# dongle.net
KiCad netlist of a schematic drawn in EAGLE
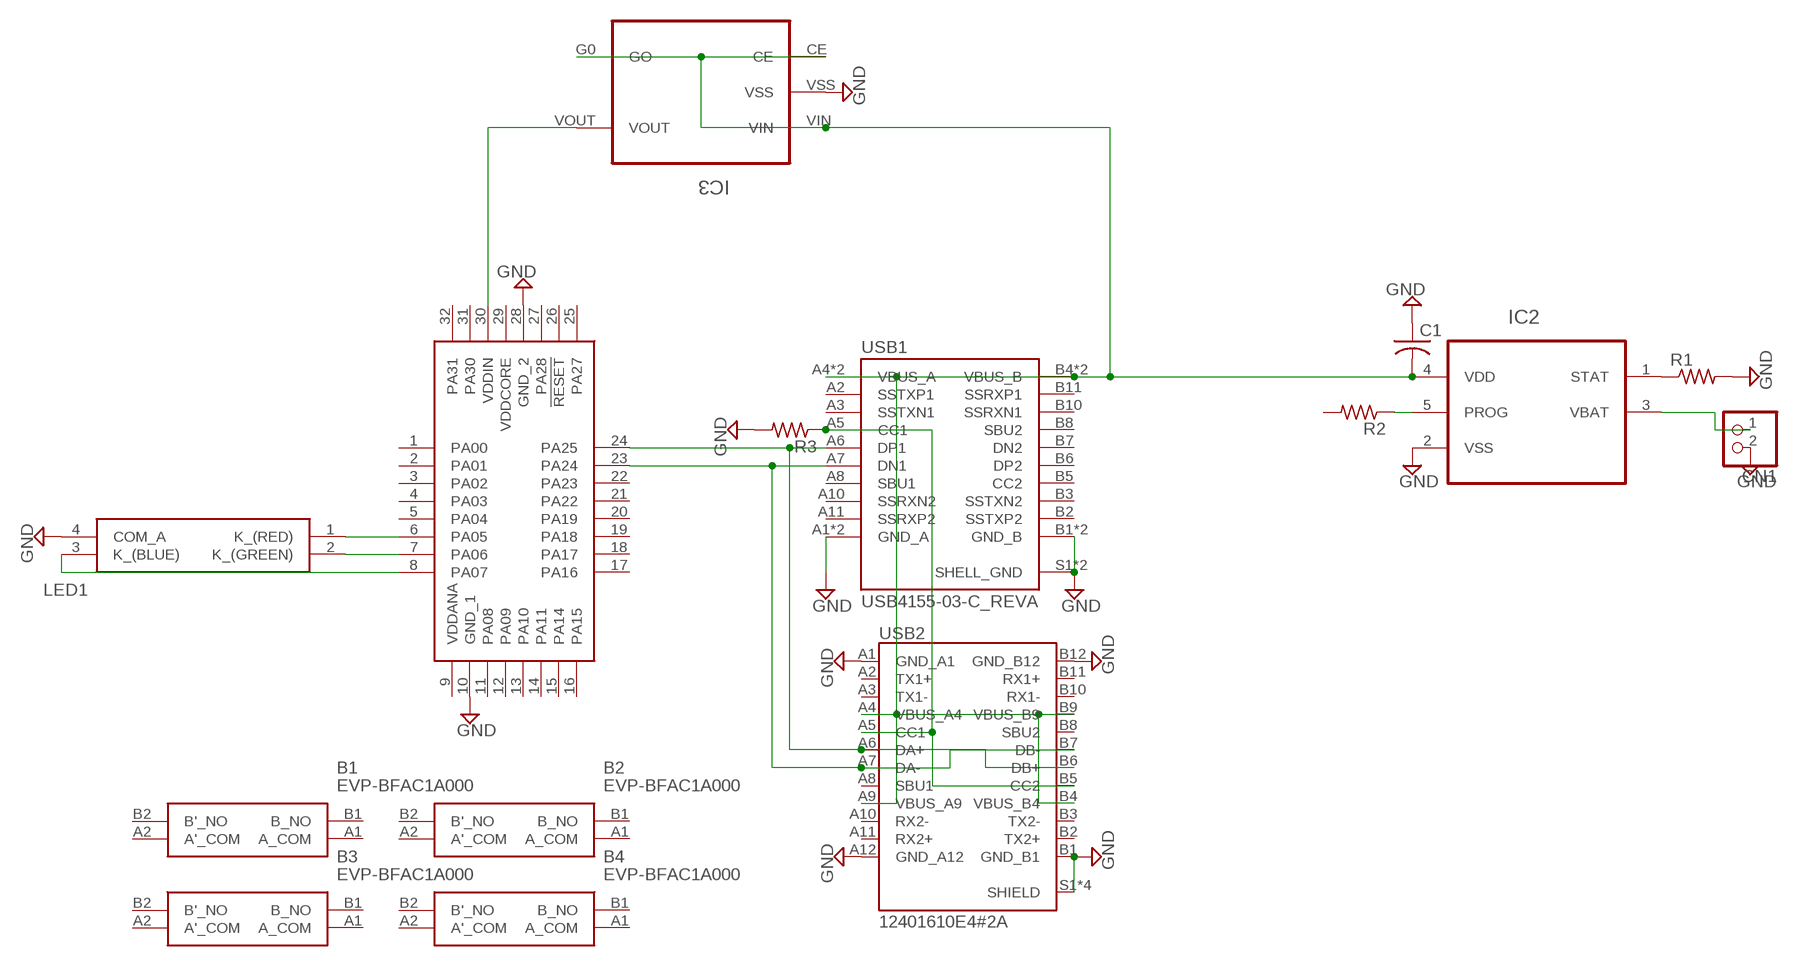
[diagram p0: schematic, sheet 1]

(export (version "E")
  (design (tool "Eeschema 10.0.6"))
  (components
    (comp (ref "B1")
      (value "EVP-BFAC1A000")
      (footprint "eagle-import:EVPBFAC1A000")
      (fields (field (name "MOUSER_PART_NUMBER") "667-EVP-BFAC1A000"))
      (libsource (lib "eagle-import") (part "EVP-BFAC1A000"))
    )
    (comp (ref "B2")
      (value "EVP-BFAC1A000")
      (footprint "eagle-import:EVPBFAC1A000")
      (fields (field (name "MOUSER_PART_NUMBER") "667-EVP-BFAC1A000"))
      (libsource (lib "eagle-import") (part "EVP-BFAC1A000"))
    )
    (comp (ref "B3")
      (value "EVP-BFAC1A000")
      (footprint "eagle-import:EVPBFAC1A000")
      (fields (field (name "MOUSER_PART_NUMBER") "667-EVP-BFAC1A000"))
      (libsource (lib "eagle-import") (part "EVP-BFAC1A000"))
    )
    (comp (ref "B4")
      (value "EVP-BFAC1A000")
      (footprint "eagle-import:EVPBFAC1A000")
      (fields (field (name "MOUSER_PART_NUMBER") "667-EVP-BFAC1A000"))
      (libsource (lib "eagle-import") (part "EVP-BFAC1A000"))
    )
    (comp (ref "C1")
      (value "C-USC0805")
      (footprint "eagle-import:C0805")
      (libsource (lib "eagle-import") (part "C-USC0805"))
    )
    (comp (ref "CN1")
      (value "JST_2PIN-SMT-RA")
      (footprint "eagle-import:JST-PH-2-SMT-RA")
      (libsource (lib "eagle-import") (part "JST_2PIN-SMT-RA"))
    )
    (comp (ref "IC1")
      (value "ATSAMD21E18A-AFT")
      (footprint "eagle-import:QFP80P900X900X120-32N")
      (fields (field (name "MOUSER_PART_NUMBER") "556-ATSAMD21E18A-AFT"))
      (libsource (lib "eagle-import") (part "ATSAMD21E18A-AFT"))
    )
    (comp (ref "IC2")
      (value "MCP73831T-2ACI/OT")
      (footprint "eagle-import:SOT95P280X145-5N")
      (fields (field (name "MF") "Microchip"))
      (libsource (lib "eagle-import") (part "MCP73831T-2ACI/OT"))
    )
    (comp (ref "IC3")
      (value "IC_XC8107AC20MR-G")
      (footprint "eagle-import:IC_XC8107AC20MR-G")
      (libsource (lib "eagle-import") (part "IC_XC8107AC20MR-G"))
    )
    (comp (ref "LED1")
      (value "ASMB-MTB1-0B3A2")
      (footprint "eagle-import:ASMBMTB10B3A2")
      (fields (field (name "MOUSER_PART_NUMBER") "630-ASMB-MTB1-0B3A2"))
      (libsource (lib "eagle-import") (part "ASMB-MTB1-0B3A2"))
    )
    (comp (ref "R1")
      (value "R-US_R0805")
      (footprint "eagle-import:R0805")
      (libsource (lib "eagle-import") (part "R-US_R0805"))
    )
    (comp (ref "R2")
      (value "R-US_R0805")
      (footprint "eagle-import:R0805")
      (libsource (lib "eagle-import") (part "R-US_R0805"))
    )
    (comp (ref "R3")
      (value "R-US_R0805")
      (footprint "eagle-import:R0805")
      (libsource (lib "eagle-import") (part "R-US_R0805"))
    )
    (comp (ref "USB1")
      (value "USB4155-03-C_REVA")
      (footprint "eagle-import:GCT_USB4155-03-C_REVA")
      (fields (field (name "MF") "Global Connector Technology") (field (name "MP") "USB4155-03-C"))
      (libsource (lib "eagle-import") (part "USB4155-03-C_REVA"))
    )
    (comp (ref "USB2")
      (value "12401610E4#2A")
      (footprint "eagle-import:AMPHENOL_12401610E4#2A")
      (fields (field (name "MF") "Amphenol ICC (Commercial Products)"))
      (libsource (lib "eagle-import") (part "12401610E4#2A"))
    )
  )
  (nets
    (net (code "1") (name "GND") (class "Default")
      (node (ref "C1") (pin "1") (pinfunction "1_1") (pintype "passive"))
      (node (ref "CN1") (pin "2") (pinfunction "1_2") (pintype "passive"))
      (node (ref "IC1") (pin "10") (pinfunction "GND_1_10") (pintype "bidirectional"))
      (node (ref "IC1") (pin "28") (pinfunction "GND_2_28") (pintype "bidirectional"))
      (node (ref "IC2") (pin "2") (pinfunction "VSS_2") (pintype "power_in"))
      (node (ref "IC3") (pin "VSS") (pinfunction "VSS_VSS") (pintype "input"))
      (node (ref "LED1") (pin "4") (pinfunction "COM_A_4") (pintype "bidirectional"))
      (node (ref "R1") (pin "2") (pinfunction "2_2") (pintype "passive"))
      (node (ref "R3") (pin "2") (pinfunction "2_2") (pintype "passive"))
      (node (ref "USB1") (pin "A1") (pinfunction "GND_A_A1") (pintype "power_in"))
      (node (ref "USB1") (pin "A12") (pinfunction "GND_A_A12") (pintype "power_in"))
      (node (ref "USB1") (pin "B1") (pinfunction "GND_B_B1") (pintype "power_in"))
      (node (ref "USB1") (pin "B12") (pinfunction "GND_B_B12") (pintype "power_in"))
      (node (ref "USB1") (pin "S1") (pinfunction "SHELL_GND_S1") (pintype "power_in"))
      (node (ref "USB1") (pin "S2") (pinfunction "SHELL_GND_S2") (pintype "power_in"))
      (node (ref "USB2") (pin "A1") (pinfunction "GND_A1_A1") (pintype "passive"))
      (node (ref "USB2") (pin "A12") (pinfunction "GND_A12_A12") (pintype "passive"))
      (node (ref "USB2") (pin "B1") (pinfunction "GND_B1_B1") (pintype "passive"))
      (node (ref "USB2") (pin "B12") (pinfunction "GND_B12_B12") (pintype "passive"))
      (node (ref "USB2") (pin "S1") (pinfunction "SHIELD_S1") (pintype "passive"))
      (node (ref "USB2") (pin "S2") (pinfunction "SHIELD_S2") (pintype "passive"))
      (node (ref "USB2") (pin "S3") (pinfunction "SHIELD_S3") (pintype "passive"))
      (node (ref "USB2") (pin "S4") (pinfunction "SHIELD_S4") (pintype "passive"))
    )
    (net (code "2") (name "Net-(CN1-2)") (class "Default")
      (node (ref "CN1") (pin "1") (pinfunction "2_1") (pintype "passive"))
      (node (ref "IC2") (pin "3") (pinfunction "VBAT_3") (pintype "output"))
    )
    (net (code "3") (name "Net-(IC1-PA05)") (class "Default")
      (node (ref "IC1") (pin "6") (pinfunction "PA05_6") (pintype "bidirectional"))
      (node (ref "LED1") (pin "1") (pinfunction "K_(RED)_1") (pintype "bidirectional"))
    )
    (net (code "4") (name "Net-(IC1-PA06)") (class "Default")
      (node (ref "IC1") (pin "7") (pinfunction "PA06_7") (pintype "bidirectional"))
      (node (ref "LED1") (pin "2") (pinfunction "K_(GREEN)_2") (pintype "bidirectional"))
    )
    (net (code "5") (name "Net-(IC1-PA07)") (class "Default")
      (node (ref "IC1") (pin "8") (pinfunction "PA07_8") (pintype "bidirectional"))
      (node (ref "LED1") (pin "3") (pinfunction "K_(BLUE)_3") (pintype "bidirectional"))
    )
    (net (code "6") (name "Net-(IC1-PA24)") (class "Default")
      (node (ref "IC1") (pin "23") (pinfunction "PA24_23") (pintype "bidirectional"))
      (node (ref "USB1") (pin "A7") (pinfunction "DN1_A7") (pintype "bidirectional"))
      (node (ref "USB2") (pin "A7") (pinfunction "DA-_A7") (pintype "passive"))
      (node (ref "USB2") (pin "B7") (pinfunction "DB-_B7") (pintype "passive"))
    )
    (net (code "7") (name "Net-(IC1-PA25)") (class "Default")
      (node (ref "IC1") (pin "24") (pinfunction "PA25_24") (pintype "bidirectional"))
      (node (ref "USB1") (pin "A6") (pinfunction "DP1_A6") (pintype "bidirectional"))
      (node (ref "USB2") (pin "A6") (pinfunction "DA+_A6") (pintype "passive"))
      (node (ref "USB2") (pin "B6") (pinfunction "DB+_B6") (pintype "passive"))
    )
    (net (code "8") (name "Net-(IC1-VDDIN)") (class "Default")
      (node (ref "IC1") (pin "30") (pinfunction "VDDIN_30") (pintype "bidirectional"))
      (node (ref "IC3") (pin "VOUT") (pinfunction "VOUT_VOUT") (pintype "output"))
    )
    (net (code "9") (name "Net-(IC2-PROG)") (class "Default")
      (node (ref "IC2") (pin "5") (pinfunction "PROG_5") (pintype "input"))
      (node (ref "R2") (pin "1") (pinfunction "1_1") (pintype "passive"))
    )
    (net (code "10") (name "Net-(IC2-STAT)") (class "Default")
      (node (ref "IC2") (pin "1") (pinfunction "STAT_1") (pintype "output"))
      (node (ref "R1") (pin "1") (pinfunction "1_1") (pintype "passive"))
    )
    (net (code "11") (name "Net-(IC2-VDD)") (class "Default")
      (node (ref "C1") (pin "2") (pinfunction "2_2") (pintype "passive"))
      (node (ref "IC2") (pin "4") (pinfunction "VDD_4") (pintype "power_in"))
      (node (ref "IC3") (pin "CE") (pinfunction "CE_CE") (pintype "power_in"))
      (node (ref "IC3") (pin "G0") (pinfunction "GO_G0") (pintype "output"))
      (node (ref "IC3") (pin "VIN") (pinfunction "VIN_VIN") (pintype "power_in"))
      (node (ref "USB1") (pin "A4") (pinfunction "VBUS_A_A4") (pintype "power_in"))
      (node (ref "USB1") (pin "A9") (pinfunction "VBUS_A_A9") (pintype "power_in"))
      (node (ref "USB1") (pin "B4") (pinfunction "VBUS_B_B4") (pintype "power_in"))
      (node (ref "USB1") (pin "B9") (pinfunction "VBUS_B_B9") (pintype "power_in"))
      (node (ref "USB2") (pin "A4") (pinfunction "VBUS_A4_A4") (pintype "passive"))
      (node (ref "USB2") (pin "A9") (pinfunction "VBUS_A9_A9") (pintype "passive"))
      (node (ref "USB2") (pin "B4") (pinfunction "VBUS_B4_B4") (pintype "passive"))
      (node (ref "USB2") (pin "B9") (pinfunction "VBUS_B9_B9") (pintype "passive"))
    )
    (net (code "12") (name "Net-(USB1-CC1)") (class "Default")
      (node (ref "R3") (pin "1") (pinfunction "1_1") (pintype "passive"))
      (node (ref "USB1") (pin "A5") (pinfunction "CC1_A5") (pintype "bidirectional"))
      (node (ref "USB2") (pin "A5") (pinfunction "CC1_A5") (pintype "passive"))
      (node (ref "USB2") (pin "B5") (pinfunction "CC2_B5") (pintype "passive"))
    )
    (net (code "13") (name "unconnected-(B1-A'_COM-PadA2)") (class "Default")
      (node (ref "B1") (pin "A2") (pinfunction "A'_COM_A2") (pintype "bidirectional"))
    )
    (net (code "14") (name "unconnected-(B1-A_COM-PadA1)") (class "Default")
      (node (ref "B1") (pin "A1") (pinfunction "A_COM_A1") (pintype "bidirectional"))
    )
    (net (code "15") (name "unconnected-(B1-B'_NO-PadB2)") (class "Default")
      (node (ref "B1") (pin "B2") (pinfunction "B'_NO_B2") (pintype "bidirectional"))
    )
    (net (code "16") (name "unconnected-(B1-B_NO-PadB1)") (class "Default")
      (node (ref "B1") (pin "B1") (pinfunction "B_NO_B1") (pintype "bidirectional"))
    )
    (net (code "17") (name "unconnected-(B2-A'_COM-PadA2)") (class "Default")
      (node (ref "B2") (pin "A2") (pinfunction "A'_COM_A2") (pintype "bidirectional"))
    )
    (net (code "18") (name "unconnected-(B2-A_COM-PadA1)") (class "Default")
      (node (ref "B2") (pin "A1") (pinfunction "A_COM_A1") (pintype "bidirectional"))
    )
    (net (code "19") (name "unconnected-(B2-B'_NO-PadB2)") (class "Default")
      (node (ref "B2") (pin "B2") (pinfunction "B'_NO_B2") (pintype "bidirectional"))
    )
    (net (code "20") (name "unconnected-(B2-B_NO-PadB1)") (class "Default")
      (node (ref "B2") (pin "B1") (pinfunction "B_NO_B1") (pintype "bidirectional"))
    )
    (net (code "21") (name "unconnected-(B3-A'_COM-PadA2)") (class "Default")
      (node (ref "B3") (pin "A2") (pinfunction "A'_COM_A2") (pintype "bidirectional"))
    )
    (net (code "22") (name "unconnected-(B3-A_COM-PadA1)") (class "Default")
      (node (ref "B3") (pin "A1") (pinfunction "A_COM_A1") (pintype "bidirectional"))
    )
    (net (code "23") (name "unconnected-(B3-B'_NO-PadB2)") (class "Default")
      (node (ref "B3") (pin "B2") (pinfunction "B'_NO_B2") (pintype "bidirectional"))
    )
    (net (code "24") (name "unconnected-(B3-B_NO-PadB1)") (class "Default")
      (node (ref "B3") (pin "B1") (pinfunction "B_NO_B1") (pintype "bidirectional"))
    )
    (net (code "25") (name "unconnected-(B4-A'_COM-PadA2)") (class "Default")
      (node (ref "B4") (pin "A2") (pinfunction "A'_COM_A2") (pintype "bidirectional"))
    )
    (net (code "26") (name "unconnected-(B4-A_COM-PadA1)") (class "Default")
      (node (ref "B4") (pin "A1") (pinfunction "A_COM_A1") (pintype "bidirectional"))
    )
    (net (code "27") (name "unconnected-(B4-B'_NO-PadB2)") (class "Default")
      (node (ref "B4") (pin "B2") (pinfunction "B'_NO_B2") (pintype "bidirectional"))
    )
    (net (code "28") (name "unconnected-(B4-B_NO-PadB1)") (class "Default")
      (node (ref "B4") (pin "B1") (pinfunction "B_NO_B1") (pintype "bidirectional"))
    )
    (net (code "29") (name "unconnected-(IC1-PA00-Pad1)") (class "Default")
      (node (ref "IC1") (pin "1") (pinfunction "PA00_1") (pintype "bidirectional"))
    )
    (net (code "30") (name "unconnected-(IC1-PA01-Pad2)") (class "Default")
      (node (ref "IC1") (pin "2") (pinfunction "PA01_2") (pintype "bidirectional"))
    )
    (net (code "31") (name "unconnected-(IC1-PA02-Pad3)") (class "Default")
      (node (ref "IC1") (pin "3") (pinfunction "PA02_3") (pintype "bidirectional"))
    )
    (net (code "32") (name "unconnected-(IC1-PA03-Pad4)") (class "Default")
      (node (ref "IC1") (pin "4") (pinfunction "PA03_4") (pintype "bidirectional"))
    )
    (net (code "33") (name "unconnected-(IC1-PA04-Pad5)") (class "Default")
      (node (ref "IC1") (pin "5") (pinfunction "PA04_5") (pintype "bidirectional"))
    )
    (net (code "34") (name "unconnected-(IC1-PA08-Pad11)") (class "Default")
      (node (ref "IC1") (pin "11") (pinfunction "PA08_11") (pintype "bidirectional"))
    )
    (net (code "35") (name "unconnected-(IC1-PA09-Pad12)") (class "Default")
      (node (ref "IC1") (pin "12") (pinfunction "PA09_12") (pintype "bidirectional"))
    )
    (net (code "36") (name "unconnected-(IC1-PA10-Pad13)") (class "Default")
      (node (ref "IC1") (pin "13") (pinfunction "PA10_13") (pintype "bidirectional"))
    )
    (net (code "37") (name "unconnected-(IC1-PA11-Pad14)") (class "Default")
      (node (ref "IC1") (pin "14") (pinfunction "PA11_14") (pintype "bidirectional"))
    )
    (net (code "38") (name "unconnected-(IC1-PA14-Pad15)") (class "Default")
      (node (ref "IC1") (pin "15") (pinfunction "PA14_15") (pintype "bidirectional"))
    )
    (net (code "39") (name "unconnected-(IC1-PA15-Pad16)") (class "Default")
      (node (ref "IC1") (pin "16") (pinfunction "PA15_16") (pintype "bidirectional"))
    )
    (net (code "40") (name "unconnected-(IC1-PA16-Pad17)") (class "Default")
      (node (ref "IC1") (pin "17") (pinfunction "PA16_17") (pintype "bidirectional"))
    )
    (net (code "41") (name "unconnected-(IC1-PA17-Pad18)") (class "Default")
      (node (ref "IC1") (pin "18") (pinfunction "PA17_18") (pintype "bidirectional"))
    )
    (net (code "42") (name "unconnected-(IC1-PA18-Pad19)") (class "Default")
      (node (ref "IC1") (pin "19") (pinfunction "PA18_19") (pintype "bidirectional"))
    )
    (net (code "43") (name "unconnected-(IC1-PA19-Pad20)") (class "Default")
      (node (ref "IC1") (pin "20") (pinfunction "PA19_20") (pintype "bidirectional"))
    )
    (net (code "44") (name "unconnected-(IC1-PA22-Pad21)") (class "Default")
      (node (ref "IC1") (pin "21") (pinfunction "PA22_21") (pintype "bidirectional"))
    )
    (net (code "45") (name "unconnected-(IC1-PA23-Pad22)") (class "Default")
      (node (ref "IC1") (pin "22") (pinfunction "PA23_22") (pintype "bidirectional"))
    )
    (net (code "46") (name "unconnected-(IC1-PA27-Pad25)") (class "Default")
      (node (ref "IC1") (pin "25") (pinfunction "PA27_25") (pintype "bidirectional"))
    )
    (net (code "47") (name "unconnected-(IC1-PA28-Pad27)") (class "Default")
      (node (ref "IC1") (pin "27") (pinfunction "PA28_27") (pintype "bidirectional"))
    )
    (net (code "48") (name "unconnected-(IC1-PA30-Pad31)") (class "Default")
      (node (ref "IC1") (pin "31") (pinfunction "PA30_31") (pintype "bidirectional"))
    )
    (net (code "49") (name "unconnected-(IC1-PA31-Pad32)") (class "Default")
      (node (ref "IC1") (pin "32") (pinfunction "PA31_32") (pintype "bidirectional"))
    )
    (net (code "50") (name "unconnected-(IC1-VDDANA-Pad9)") (class "Default")
      (node (ref "IC1") (pin "9") (pinfunction "VDDANA_9") (pintype "bidirectional"))
    )
    (net (code "51") (name "unconnected-(IC1-VDDCORE-Pad29)") (class "Default")
      (node (ref "IC1") (pin "29") (pinfunction "VDDCORE_29") (pintype "bidirectional"))
    )
    (net (code "52") (name "unconnected-(IC1-~{RESET}-Pad26)") (class "Default")
      (node (ref "IC1") (pin "26") (pinfunction "~{RESET}_26") (pintype "bidirectional"))
    )
    (net (code "53") (name "unconnected-(R2-Pad2)") (class "Default")
      (node (ref "R2") (pin "2") (pinfunction "2_2") (pintype "passive"))
    )
    (net (code "54") (name "unconnected-(USB1-CC2-PadB5)") (class "Default")
      (node (ref "USB1") (pin "B5") (pinfunction "CC2_B5") (pintype "bidirectional"))
    )
    (net (code "55") (name "unconnected-(USB1-DN2-PadB7)") (class "Default")
      (node (ref "USB1") (pin "B7") (pinfunction "DN2_B7") (pintype "bidirectional"))
    )
    (net (code "56") (name "unconnected-(USB1-DP2-PadB6)") (class "Default")
      (node (ref "USB1") (pin "B6") (pinfunction "DP2_B6") (pintype "bidirectional"))
    )
    (net (code "57") (name "unconnected-(USB1-SBU1-PadA8)") (class "Default")
      (node (ref "USB1") (pin "A8") (pinfunction "SBU1_A8") (pintype "bidirectional"))
    )
    (net (code "58") (name "unconnected-(USB1-SBU2-PadB8)") (class "Default")
      (node (ref "USB1") (pin "B8") (pinfunction "SBU2_B8") (pintype "bidirectional"))
    )
    (net (code "59") (name "unconnected-(USB1-SSRXN1-PadB10)") (class "Default")
      (node (ref "USB1") (pin "B10") (pinfunction "SSRXN1_B10") (pintype "bidirectional"))
    )
    (net (code "60") (name "unconnected-(USB1-SSRXN2-PadA10)") (class "Default")
      (node (ref "USB1") (pin "A10") (pinfunction "SSRXN2_A10") (pintype "bidirectional"))
    )
    (net (code "61") (name "unconnected-(USB1-SSRXP1-PadB11)") (class "Default")
      (node (ref "USB1") (pin "B11") (pinfunction "SSRXP1_B11") (pintype "bidirectional"))
    )
    (net (code "62") (name "unconnected-(USB1-SSRXP2-PadA11)") (class "Default")
      (node (ref "USB1") (pin "A11") (pinfunction "SSRXP2_A11") (pintype "bidirectional"))
    )
    (net (code "63") (name "unconnected-(USB1-SSTXN1-PadA3)") (class "Default")
      (node (ref "USB1") (pin "A3") (pinfunction "SSTXN1_A3") (pintype "bidirectional"))
    )
    (net (code "64") (name "unconnected-(USB1-SSTXN2-PadB3)") (class "Default")
      (node (ref "USB1") (pin "B3") (pinfunction "SSTXN2_B3") (pintype "bidirectional"))
    )
    (net (code "65") (name "unconnected-(USB1-SSTXP1-PadA2)") (class "Default")
      (node (ref "USB1") (pin "A2") (pinfunction "SSTXP1_A2") (pintype "bidirectional"))
    )
    (net (code "66") (name "unconnected-(USB1-SSTXP2-PadB2)") (class "Default")
      (node (ref "USB1") (pin "B2") (pinfunction "SSTXP2_B2") (pintype "bidirectional"))
    )
    (net (code "67") (name "unconnected-(USB2-RX1+-PadB11)") (class "Default")
      (node (ref "USB2") (pin "B11") (pinfunction "RX1+_B11") (pintype "passive"))
    )
    (net (code "68") (name "unconnected-(USB2-RX1--PadB10)") (class "Default")
      (node (ref "USB2") (pin "B10") (pinfunction "RX1-_B10") (pintype "passive"))
    )
    (net (code "69") (name "unconnected-(USB2-RX2+-PadA11)") (class "Default")
      (node (ref "USB2") (pin "A11") (pinfunction "RX2+_A11") (pintype "passive"))
    )
    (net (code "70") (name "unconnected-(USB2-RX2--PadA10)") (class "Default")
      (node (ref "USB2") (pin "A10") (pinfunction "RX2-_A10") (pintype "passive"))
    )
    (net (code "71") (name "unconnected-(USB2-SBU1-PadA8)") (class "Default")
      (node (ref "USB2") (pin "A8") (pinfunction "SBU1_A8") (pintype "passive"))
    )
    (net (code "72") (name "unconnected-(USB2-SBU2-PadB8)") (class "Default")
      (node (ref "USB2") (pin "B8") (pinfunction "SBU2_B8") (pintype "passive"))
    )
    (net (code "73") (name "unconnected-(USB2-TX1+-PadA2)") (class "Default")
      (node (ref "USB2") (pin "A2") (pinfunction "TX1+_A2") (pintype "passive"))
    )
    (net (code "74") (name "unconnected-(USB2-TX1--PadA3)") (class "Default")
      (node (ref "USB2") (pin "A3") (pinfunction "TX1-_A3") (pintype "passive"))
    )
    (net (code "75") (name "unconnected-(USB2-TX2+-PadB2)") (class "Default")
      (node (ref "USB2") (pin "B2") (pinfunction "TX2+_B2") (pintype "passive"))
    )
    (net (code "76") (name "unconnected-(USB2-TX2--PadB3)") (class "Default")
      (node (ref "USB2") (pin "B3") (pinfunction "TX2-_B3") (pintype "passive"))
    )
  )
)
